# bbf-eurojacks.net
KiCad netlist of a schematic drawn in EAGLE
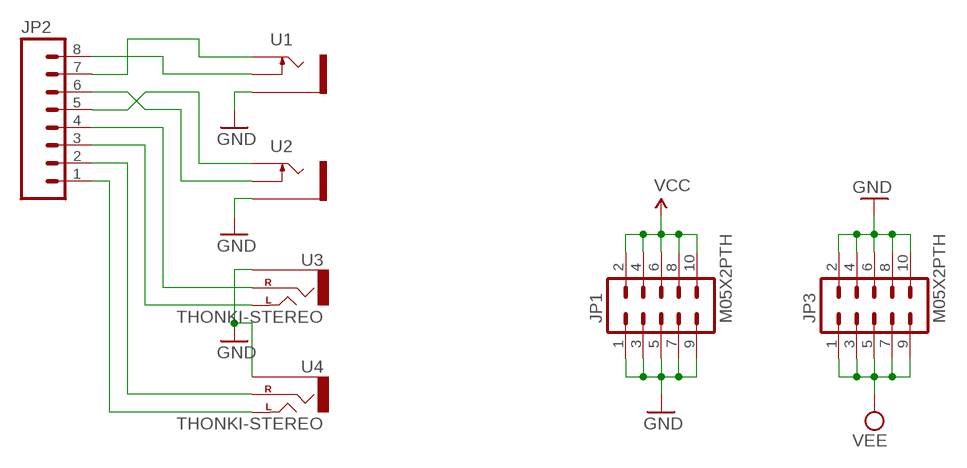
[diagram p0: schematic, sheet 1]

(export (version "E")
  (design (tool "Eeschema 10.0.6"))
  (components
    (comp (ref "JP1")
      (value "M05X2PTH")
      (footprint "eagle-import:AVR_ICSP")
      (libsource (lib "eagle-import") (part "M05X2PTH"))
    )
    (comp (ref "JP2")
      (value "M08")
      (footprint "eagle-import:1X08")
      (libsource (lib "eagle-import") (part "M08"))
    )
    (comp (ref "JP3")
      (value "M05X2PTH")
      (footprint "eagle-import:AVR_ICSP")
      (libsource (lib "eagle-import") (part "M05X2PTH"))
    )
    (comp (ref "U1")
      (value "THONKICONNNEW")
      (footprint "eagle-import:WQP-PJ301M-12_JACK")
      (libsource (lib "eagle-import") (part "THONKICONNNEW"))
    )
    (comp (ref "U2")
      (value "THONKICONNNEW")
      (footprint "eagle-import:WQP-PJ301M-12_JACK")
      (libsource (lib "eagle-import") (part "THONKICONNNEW"))
    )
    (comp (ref "U3")
      (value "THONKI-STEREO")
      (footprint "eagle-import:WQP-PJ366ST_JACK")
      (libsource (lib "eagle-import") (part "THONKI-STEREO"))
    )
    (comp (ref "U4")
      (value "THONKI-STEREO")
      (footprint "eagle-import:WQP-PJ366ST_JACK")
      (libsource (lib "eagle-import") (part "THONKI-STEREO"))
    )
  )
  (nets
    (net (code "1") (name "GND") (class "Default")
      (node (ref "JP1") (pin "1") (pinfunction "1_1") (pintype "passive"))
      (node (ref "JP1") (pin "3") (pinfunction "3_3") (pintype "passive"))
      (node (ref "JP1") (pin "5") (pinfunction "5_5") (pintype "passive"))
      (node (ref "JP1") (pin "7") (pinfunction "7_7") (pintype "passive"))
      (node (ref "JP1") (pin "9") (pinfunction "9_9") (pintype "passive"))
      (node (ref "JP3") (pin "10") (pinfunction "10_10") (pintype "passive"))
      (node (ref "JP3") (pin "2") (pinfunction "2_2") (pintype "passive"))
      (node (ref "JP3") (pin "4") (pinfunction "4_4") (pintype "passive"))
      (node (ref "JP3") (pin "6") (pinfunction "6_6") (pintype "passive"))
      (node (ref "JP3") (pin "8") (pinfunction "8_8") (pintype "passive"))
      (node (ref "U1") (pin "P$3_SLEEVE") (pinfunction "SLEEVE_P$3_SLEEVE") (pintype "passive"))
      (node (ref "U2") (pin "P$3_SLEEVE") (pinfunction "SLEEVE_P$3_SLEEVE") (pintype "passive"))
      (node (ref "U3") (pin "P$3_SLEEVE") (pinfunction "SLEEVE_P$3_SLEEVE") (pintype "bidirectional"))
      (node (ref "U4") (pin "P$3_SLEEVE") (pinfunction "SLEEVE_P$3_SLEEVE") (pintype "bidirectional"))
    )
    (net (code "2") (name "Net-(U1-SWITCH)") (class "Default")
      (node (ref "JP2") (pin "8") (pinfunction "8_8") (pintype "passive"))
      (node (ref "U1") (pin "P$2_SWITCH") (pinfunction "SWITCH_P$2_SWITCH") (pintype "passive"))
    )
    (net (code "3") (name "Net-(U1-TIP)") (class "Default")
      (node (ref "JP2") (pin "7") (pinfunction "7_7") (pintype "passive"))
      (node (ref "U1") (pin "P$1_TIP") (pinfunction "TIP_P$1_TIP") (pintype "passive"))
    )
    (net (code "4") (name "Net-(U2-SWITCH)") (class "Default")
      (node (ref "JP2") (pin "6") (pinfunction "6_6") (pintype "passive"))
      (node (ref "U2") (pin "P$2_SWITCH") (pinfunction "SWITCH_P$2_SWITCH") (pintype "passive"))
    )
    (net (code "5") (name "Net-(U2-TIP)") (class "Default")
      (node (ref "JP2") (pin "5") (pinfunction "5_5") (pintype "passive"))
      (node (ref "U2") (pin "P$1_TIP") (pinfunction "TIP_P$1_TIP") (pintype "passive"))
    )
    (net (code "6") (name "Net-(U3-LEFT)") (class "Default")
      (node (ref "JP2") (pin "3") (pinfunction "3_3") (pintype "passive"))
      (node (ref "U3") (pin "P$1_TIP") (pinfunction "LEFT_P$1_TIP") (pintype "bidirectional"))
    )
    (net (code "7") (name "Net-(U3-RIGHT)") (class "Default")
      (node (ref "JP2") (pin "4") (pinfunction "4_4") (pintype "passive"))
      (node (ref "U3") (pin "P$2_SWITCH") (pinfunction "RIGHT_P$2_SWITCH") (pintype "bidirectional"))
    )
    (net (code "8") (name "Net-(U4-LEFT)") (class "Default")
      (node (ref "JP2") (pin "1") (pinfunction "1_1") (pintype "passive"))
      (node (ref "U4") (pin "P$1_TIP") (pinfunction "LEFT_P$1_TIP") (pintype "bidirectional"))
    )
    (net (code "9") (name "Net-(U4-RIGHT)") (class "Default")
      (node (ref "JP2") (pin "2") (pinfunction "2_2") (pintype "passive"))
      (node (ref "U4") (pin "P$2_SWITCH") (pinfunction "RIGHT_P$2_SWITCH") (pintype "bidirectional"))
    )
    (net (code "10") (name "VCC") (class "Default")
      (node (ref "JP1") (pin "10") (pinfunction "10_10") (pintype "passive"))
      (node (ref "JP1") (pin "2") (pinfunction "2_2") (pintype "passive"))
      (node (ref "JP1") (pin "4") (pinfunction "4_4") (pintype "passive"))
      (node (ref "JP1") (pin "6") (pinfunction "6_6") (pintype "passive"))
      (node (ref "JP1") (pin "8") (pinfunction "8_8") (pintype "passive"))
    )
    (net (code "11") (name "VEE") (class "Default")
      (node (ref "JP3") (pin "1") (pinfunction "1_1") (pintype "passive"))
      (node (ref "JP3") (pin "3") (pinfunction "3_3") (pintype "passive"))
      (node (ref "JP3") (pin "5") (pinfunction "5_5") (pintype "passive"))
      (node (ref "JP3") (pin "7") (pinfunction "7_7") (pintype "passive"))
      (node (ref "JP3") (pin "9") (pinfunction "9_9") (pintype "passive"))
    )
  )
)
